# OSO-MISC-20-030_PyRadio.net
KiCad netlist of a schematic drawn in EAGLE
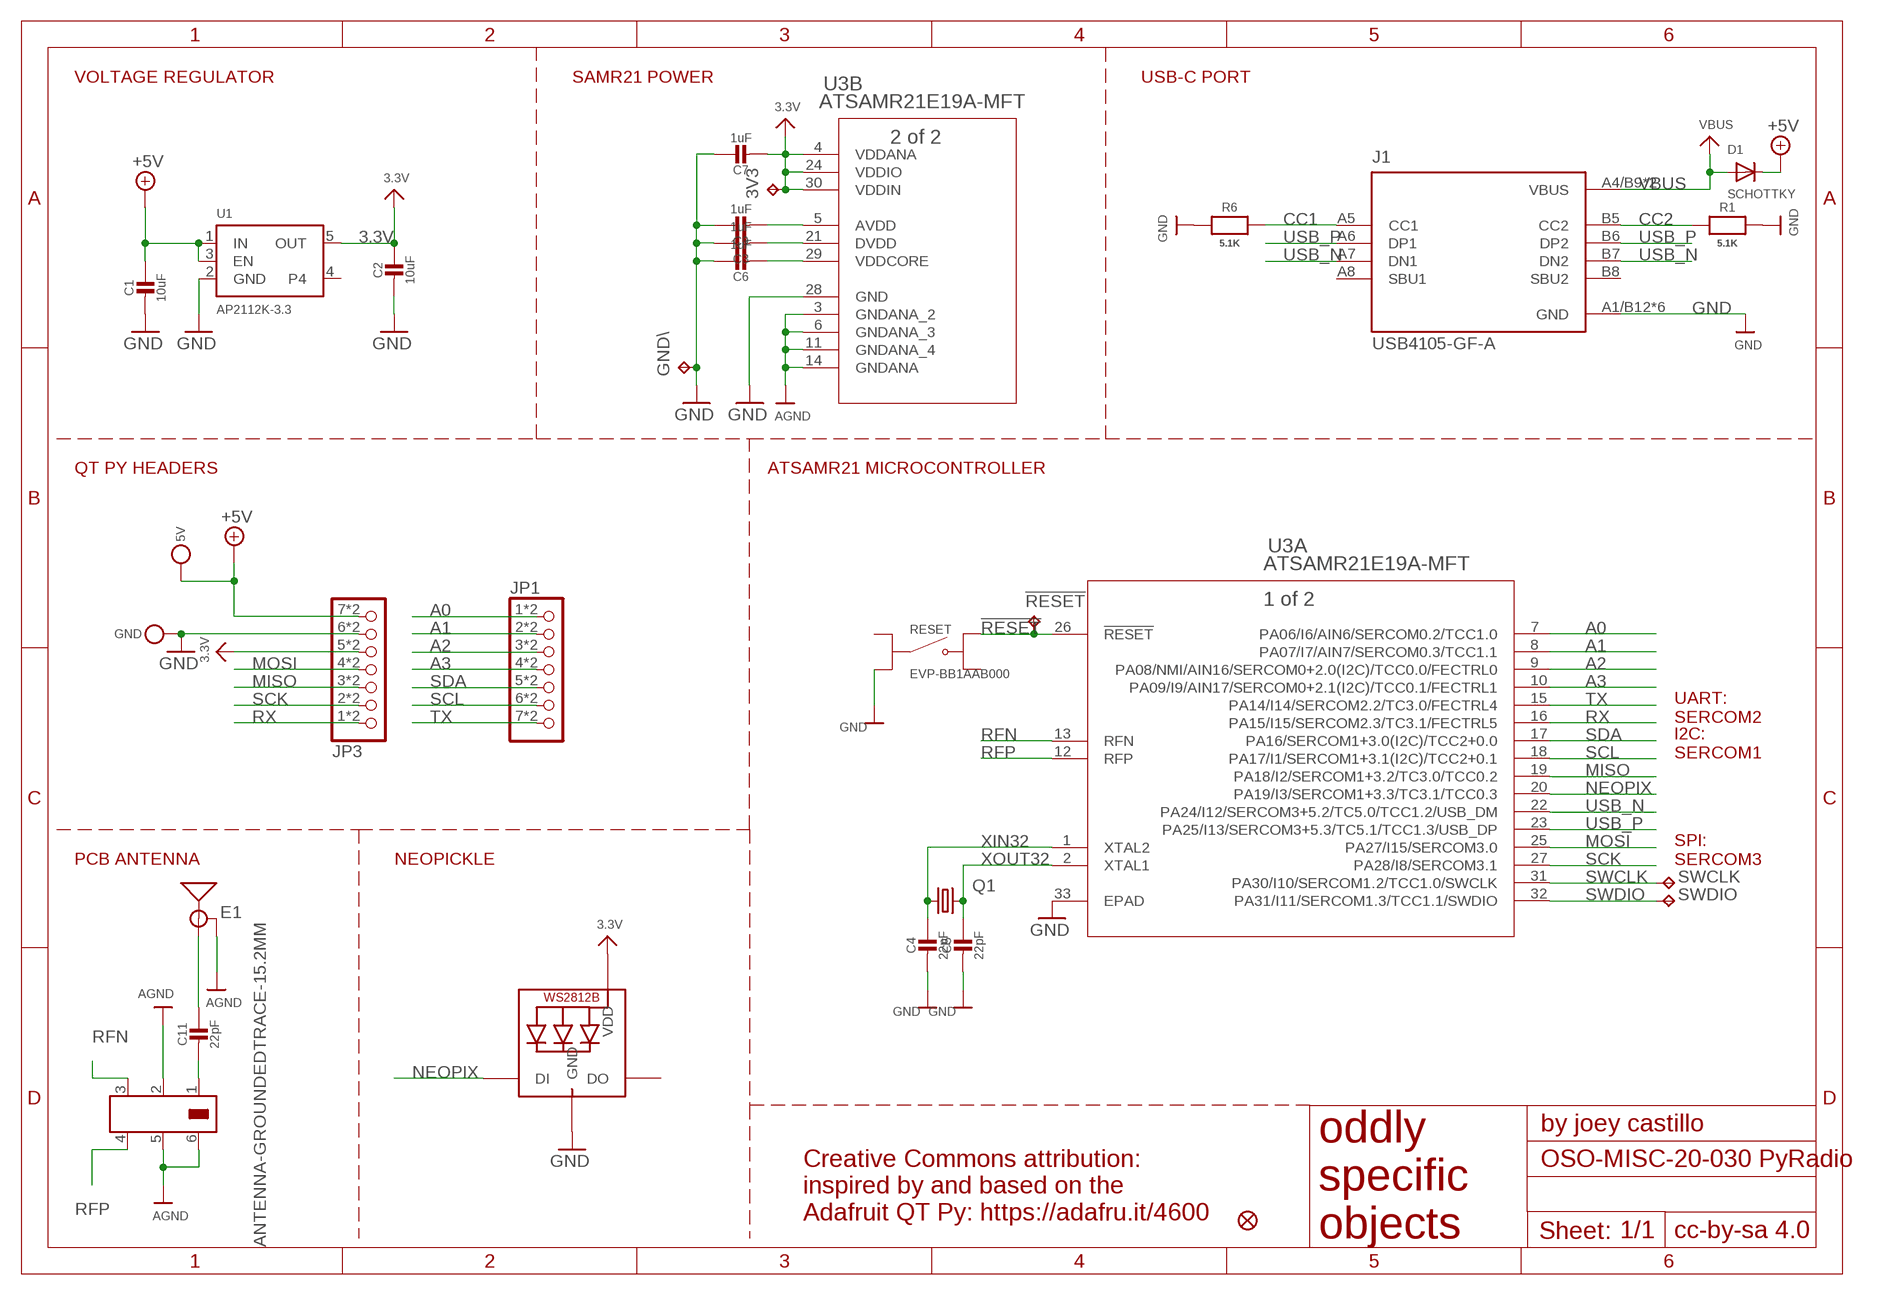
[diagram p0: schematic, sheet 1]

(export (version "E")
  (design (tool "Eeschema 10.0.6"))
  (components
    (comp (ref "!RESET")
      (value "TPTP20R")
      (footprint "eagle-import:TP20R")
      (libsource (lib "eagle-import") (part "TPTP20R"))
    )
    (comp (ref "3V3")
      (value "TPTP20R")
      (footprint "eagle-import:TP20R")
      (libsource (lib "eagle-import") (part "TPTP20R"))
    )
    (comp (ref "5V")
      (value "TESTPOINT_1X3")
      (footprint "eagle-import:TESTPOINT_RECT_1X3MM")
      (libsource (lib "eagle-import") (part "TESTPOINT_1X3"))
    )
    (comp (ref "BALUN")
      (value "JOHANSON_2450BM15A0015E")
      (footprint "eagle-import:0805_BALUN")
      (libsource (lib "eagle-import") (part "JOHANSON_2450BM15A0015E"))
    )
    (comp (ref "C1")
      (value "10uF")
      (footprint "eagle-import:_0603MP")
      (libsource (lib "eagle-import") (part "CAP_CERAMIC_0603MP"))
    )
    (comp (ref "C2")
      (value "10uF")
      (footprint "eagle-import:_0603MP")
      (libsource (lib "eagle-import") (part "CAP_CERAMIC_0603MP"))
    )
    (comp (ref "C3")
      (value "1uF")
      (footprint "eagle-import:_0603MP")
      (libsource (lib "eagle-import") (part "CAP_CERAMIC_0603MP"))
    )
    (comp (ref "C4")
      (value "22pF")
      (footprint "eagle-import:_0603MP")
      (libsource (lib "eagle-import") (part "CAP_CERAMIC_0603MP"))
    )
    (comp (ref "C5")
      (value "22pF")
      (footprint "eagle-import:_0603MP")
      (libsource (lib "eagle-import") (part "CAP_CERAMIC_0603MP"))
    )
    (comp (ref "C6")
      (value "1uF")
      (footprint "eagle-import:_0603MP")
      (libsource (lib "eagle-import") (part "CAP_CERAMIC_0603MP"))
    )
    (comp (ref "C7")
      (value "1uF")
      (footprint "eagle-import:_0603MP")
      (libsource (lib "eagle-import") (part "CAP_CERAMIC_0603MP"))
    )
    (comp (ref "C9")
      (value "1uF")
      (footprint "eagle-import:_0603MP")
      (libsource (lib "eagle-import") (part "CAP_CERAMIC_0603MP"))
    )
    (comp (ref "C11")
      (value "22pF")
      (footprint "eagle-import:_0603MP")
      (libsource (lib "eagle-import") (part "CAP_CERAMIC_0603MP"))
    )
    (comp (ref "D1")
      (value "SCHOTTKY")
      (footprint "eagle-import:SOD-323F")
      (libsource (lib "eagle-import") (part "DIODESOD-323F"))
    )
    (comp (ref "E1")
      (value "ANTENNA-GROUNDEDTRACE-15.2MM")
      (footprint "eagle-import:TRACE_ANTENNA_2.4GHZ_15.2MM")
      (libsource (lib "eagle-import") (part "ANTENNA-GROUNDEDTRACE-15.2MM"))
    )
    (comp (ref "GND")
      (value "TESTPOINT_1X3")
      (footprint "eagle-import:TESTPOINT_RECT_1X3MM")
      (libsource (lib "eagle-import") (part "TESTPOINT_1X3"))
    )
    (comp (ref "GND\\")
      (value "TPTP20R")
      (footprint "eagle-import:TP20R")
      (libsource (lib "eagle-import") (part "TPTP20R"))
    )
    (comp (ref "J1")
      (value "USB4105-GF-A")
      (footprint "eagle-import:GCT_USB4105-GF-A")
      (fields (field (name "MF") "GCT"))
      (libsource (lib "eagle-import") (part "USB4105-GF-A"))
    )
    (comp (ref "JP1")
      (value "HEADER-1X7_CASTEL")
      (footprint "eagle-import:1X07_CASTEL")
      (libsource (lib "eagle-import") (part "HEADER-1X7_CASTEL"))
    )
    (comp (ref "JP3")
      (value "HEADER-1X7_CASTEL")
      (footprint "eagle-import:1X07_CASTEL")
      (libsource (lib "eagle-import") (part "HEADER-1X7_CASTEL"))
    )
    (comp (ref "LED")
      (value "WS2812B_SK6805_1515")
      (footprint "eagle-import:SK6805_1515")
      (libsource (lib "eagle-import") (part "WS2812B_SK6805_1515"))
    )
    (comp (ref "Q1")
      (value "KX-7")
      (footprint "eagle-import:3.2X2.5_KX-7")
      (libsource (lib "eagle-import") (part "KX-7"))
    )
    (comp (ref "R1")
      (value "5.1K")
      (footprint "eagle-import:_0603MP")
      (libsource (lib "eagle-import") (part "RESISTOR_0603MP"))
    )
    (comp (ref "R6")
      (value "5.1K")
      (footprint "eagle-import:_0603MP")
      (libsource (lib "eagle-import") (part "RESISTOR_0603MP"))
    )
    (comp (ref "RESET")
      (value "EVP-BB1AAB000")
      (footprint "eagle-import:SW_EVP-BB1AAB000")
      (fields
        (field (name "DIGI-KEY_PART_NUMBER") "P124390CT-ND")
        (field (name "MF") "Panasonic Electronic Components")
      )
      (libsource (lib "eagle-import") (part "EVP-BB1AAB000"))
    )
    (comp (ref "SWCLK")
      (value "TPTP20R")
      (footprint "eagle-import:TP20R")
      (libsource (lib "eagle-import") (part "TPTP20R"))
    )
    (comp (ref "SWDIO")
      (value "TPTP20R")
      (footprint "eagle-import:TP20R")
      (libsource (lib "eagle-import") (part "TPTP20R"))
    )
    (comp (ref "U$8")
      (value "FIDUCIAL_1MM")
      (footprint "eagle-import:FIDUCIAL_1MM")
      (libsource (lib "eagle-import") (part "FIDUCIAL_1MM"))
    )
    (comp (ref "U1")
      (value "AP2112K-3.3")
      (footprint "eagle-import:SOT23-5")
      (libsource (lib "eagle-import") (part "VREG_SOT23-5"))
    )
    (comp (ref "U3")
      (value "ATSAMR21E19A-MFT")
      (footprint "eagle-import:QFN32_5X5MC_MCH")
      (fields (field (name "COPYRIGHT") "Copyright (C) 2018 Accelerated Designs. All rights reserved"))
      (libsource (lib "eagle-import") (part "ATSAMR21E19A-MFT"))
    )
  )
  (nets
    (net (code "1") (name "+5V") (class "Default")
      (node (ref "5V") (pin "P$1") (pinfunction "P$1_P$1") (pintype "bidirectional"))
      (node (ref "C1") (pin "1") (pinfunction "1_1") (pintype "passive"))
      (node (ref "D1") (pin "C") (pinfunction "C_C") (pintype "passive"))
      (node (ref "JP3") (pin "7") (pinfunction "7_7") (pintype "passive"))
      (node (ref "JP3") (pin "7C") (pinfunction "7_7C") (pintype "passive"))
      (node (ref "U1") (pin "1") (pinfunction "IN_1") (pintype "power_in"))
      (node (ref "U1") (pin "3") (pinfunction "EN_3") (pintype "input"))
    )
    (net (code "2") (name "/A0") (class "Default")
      (node (ref "JP1") (pin "1") (pinfunction "1_1") (pintype "passive"))
      (node (ref "JP1") (pin "1C") (pinfunction "1_1C") (pintype "passive"))
      (node (ref "U3") (pin "7") (pinfunction "PA06/I6/AIN6/SERCOM0.2/TCC1.0_7") (pintype "bidirectional"))
    )
    (net (code "3") (name "/A1") (class "Default")
      (node (ref "JP1") (pin "2") (pinfunction "2_2") (pintype "passive"))
      (node (ref "JP1") (pin "2C") (pinfunction "2_2C") (pintype "passive"))
      (node (ref "U3") (pin "8") (pinfunction "PA07/I7/AIN7/SERCOM0.3/TCC1.1_8") (pintype "bidirectional"))
    )
    (net (code "4") (name "/A2") (class "Default")
      (node (ref "JP1") (pin "3") (pinfunction "3_3") (pintype "passive"))
      (node (ref "JP1") (pin "3C") (pinfunction "3_3C") (pintype "passive"))
      (node (ref "U3") (pin "9") (pinfunction "PA08/NMI/AIN16/SERCOM0+2.0(I2C)/TCC0.0/FECTRL0_9") (pintype "bidirectional"))
    )
    (net (code "5") (name "/A3") (class "Default")
      (node (ref "JP1") (pin "4") (pinfunction "4_4") (pintype "passive"))
      (node (ref "JP1") (pin "4C") (pinfunction "4_4C") (pintype "passive"))
      (node (ref "U3") (pin "10") (pinfunction "PA09/I9/AIN17/SERCOM0+2.1(I2C)/TCC0.1/FECTRL1_10") (pintype "bidirectional"))
    )
    (net (code "6") (name "/CC1") (class "Default")
      (node (ref "J1") (pin "A5") (pinfunction "CC1_A5") (pintype "bidirectional"))
      (node (ref "R6") (pin "2") (pinfunction "2_2") (pintype "passive"))
    )
    (net (code "7") (name "/CC2") (class "Default")
      (node (ref "J1") (pin "B5") (pinfunction "CC2_B5") (pintype "bidirectional"))
      (node (ref "R1") (pin "1") (pinfunction "1_1") (pintype "passive"))
    )
    (net (code "8") (name "/MISO") (class "Default")
      (node (ref "JP3") (pin "3") (pinfunction "3_3") (pintype "passive"))
      (node (ref "JP3") (pin "3C") (pinfunction "3_3C") (pintype "passive"))
      (node (ref "U3") (pin "19") (pinfunction "PA18/I2/SERCOM1+3.2/TC3.0/TCC0.2_19") (pintype "bidirectional"))
    )
    (net (code "9") (name "/MOSI") (class "Default")
      (node (ref "JP3") (pin "4") (pinfunction "4_4") (pintype "passive"))
      (node (ref "JP3") (pin "4C") (pinfunction "4_4C") (pintype "passive"))
      (node (ref "U3") (pin "25") (pinfunction "PA27/I15/SERCOM3.0_25") (pintype "bidirectional"))
    )
    (net (code "10") (name "/NEOPIX") (class "Default")
      (node (ref "LED") (pin "1") (pinfunction "DI_1") (pintype "input"))
      (node (ref "U3") (pin "20") (pinfunction "PA19/I3/SERCOM1+3.3/TC3.1/TCC0.3_20") (pintype "bidirectional"))
    )
    (net (code "11") (name "/RFN") (class "Default")
      (node (ref "BALUN") (pin "3") (pinfunction "3_3") (pintype "bidirectional"))
      (node (ref "U3") (pin "13") (pinfunction "RFN_13") (pintype "passive"))
    )
    (net (code "12") (name "/RFP") (class "Default")
      (node (ref "BALUN") (pin "4") (pinfunction "4_4") (pintype "bidirectional"))
      (node (ref "U3") (pin "12") (pinfunction "RFP_12") (pintype "passive"))
    )
    (net (code "13") (name "/RX") (class "Default")
      (node (ref "JP3") (pin "1") (pinfunction "1_1") (pintype "passive"))
      (node (ref "JP3") (pin "1C") (pinfunction "1_1C") (pintype "passive"))
      (node (ref "U3") (pin "16") (pinfunction "PA15/I15/SERCOM2.3/TC3.1/FECTRL5_16") (pintype "bidirectional"))
    )
    (net (code "14") (name "/SCK") (class "Default")
      (node (ref "JP3") (pin "2") (pinfunction "2_2") (pintype "passive"))
      (node (ref "JP3") (pin "2C") (pinfunction "2_2C") (pintype "passive"))
      (node (ref "U3") (pin "27") (pinfunction "PA28/I8/SERCOM3.1_27") (pintype "bidirectional"))
    )
    (net (code "15") (name "/SCL") (class "Default")
      (node (ref "JP1") (pin "6") (pinfunction "6_6") (pintype "passive"))
      (node (ref "JP1") (pin "6C") (pinfunction "6_6C") (pintype "passive"))
      (node (ref "U3") (pin "18") (pinfunction "PA17/I1/SERCOM1+3.1(I2C)/TCC2+0.1_18") (pintype "bidirectional"))
    )
    (net (code "16") (name "/SDA") (class "Default")
      (node (ref "JP1") (pin "5") (pinfunction "5_5") (pintype "passive"))
      (node (ref "JP1") (pin "5C") (pinfunction "5_5C") (pintype "passive"))
      (node (ref "U3") (pin "17") (pinfunction "PA16/SERCOM1+3.0(I2C)/TCC2+0.0_17") (pintype "bidirectional"))
    )
    (net (code "17") (name "/SWCLK") (class "Default")
      (node (ref "SWCLK") (pin "TP") (pinfunction "TP_TP") (pintype "input"))
      (node (ref "U3") (pin "31") (pinfunction "PA30/I10/SERCOM1.2/TCC1.0/SWCLK_31") (pintype "bidirectional"))
    )
    (net (code "18") (name "/SWDIO") (class "Default")
      (node (ref "SWDIO") (pin "TP") (pinfunction "TP_TP") (pintype "input"))
      (node (ref "U3") (pin "32") (pinfunction "PA31/I11/SERCOM1.3/TCC1.1/SWDIO_32") (pintype "bidirectional"))
    )
    (net (code "19") (name "/TX") (class "Default")
      (node (ref "JP1") (pin "7") (pinfunction "7_7") (pintype "passive"))
      (node (ref "JP1") (pin "7C") (pinfunction "7_7C") (pintype "passive"))
      (node (ref "U3") (pin "15") (pinfunction "PA14/I14/SERCOM2.2/TC3.0/FECTRL4_15") (pintype "bidirectional"))
    )
    (net (code "20") (name "/USB_N") (class "Default")
      (node (ref "J1") (pin "A7") (pinfunction "DN1_A7") (pintype "bidirectional"))
      (node (ref "J1") (pin "B7") (pinfunction "DN2_B7") (pintype "bidirectional"))
      (node (ref "U3") (pin "22") (pinfunction "PA24/I12/SERCOM3+5.2/TC5.0/TCC1.2/USB_DM_22") (pintype "bidirectional"))
    )
    (net (code "21") (name "/USB_P") (class "Default")
      (node (ref "J1") (pin "A6") (pinfunction "DP1_A6") (pintype "bidirectional"))
      (node (ref "J1") (pin "B6") (pinfunction "DP2_B6") (pintype "bidirectional"))
      (node (ref "U3") (pin "23") (pinfunction "PA25/I13/SERCOM3+5.3/TC5.1/TCC1.3/USB_DP_23") (pintype "bidirectional"))
    )
    (net (code "22") (name "/XIN32") (class "Default")
      (node (ref "C4") (pin "1") (pinfunction "1_1") (pintype "passive"))
      (node (ref "Q1") (pin "1") (pinfunction "1_1") (pintype "passive"))
      (node (ref "U3") (pin "1") (pinfunction "XTAL2_1") (pintype "passive"))
    )
    (net (code "23") (name "/XOUT32") (class "Default")
      (node (ref "C5") (pin "1") (pinfunction "1_1") (pintype "passive"))
      (node (ref "Q1") (pin "3") (pinfunction "2_3") (pintype "passive"))
      (node (ref "U3") (pin "2") (pinfunction "XTAL1_2") (pintype "bidirectional"))
    )
    (net (code "24") (name "/~{RESET}") (class "Default")
      (node (ref "!RESET") (pin "TP") (pinfunction "TP_TP") (pintype "input"))
      (node (ref "RESET") (pin "B1") (pinfunction "B1_B1") (pintype "passive"))
      (node (ref "U3") (pin "26") (pinfunction "~{RESET}_26") (pintype "passive"))
    )
    (net (code "25") (name "3.3V") (class "Default")
      (node (ref "3V3") (pin "TP") (pinfunction "TP_TP") (pintype "input"))
      (node (ref "C2") (pin "1") (pinfunction "1_1") (pintype "passive"))
      (node (ref "C7") (pin "2") (pinfunction "2_2") (pintype "passive"))
      (node (ref "JP3") (pin "5") (pinfunction "5_5") (pintype "passive"))
      (node (ref "JP3") (pin "5C") (pinfunction "5_5C") (pintype "passive"))
      (node (ref "LED") (pin "2") (pinfunction "VDD_2") (pintype "power_in"))
      (node (ref "U1") (pin "5") (pinfunction "OUT_5") (pintype "power_in"))
      (node (ref "U3") (pin "24") (pinfunction "VDDIO_24") (pintype "power_in"))
      (node (ref "U3") (pin "30") (pinfunction "VDDIN_30") (pintype "power_in"))
      (node (ref "U3") (pin "4") (pinfunction "VDDANA_4") (pintype "power_in"))
    )
    (net (code "26") (name "AGND") (class "Default")
      (node (ref "BALUN") (pin "2") (pinfunction "2_2") (pintype "bidirectional"))
      (node (ref "BALUN") (pin "5") (pinfunction "5_5") (pintype "bidirectional"))
      (node (ref "BALUN") (pin "6") (pinfunction "6_6") (pintype "bidirectional"))
      (node (ref "E1") (pin "GND") (pinfunction "GND_GND") (pintype "bidirectional"))
      (node (ref "U3") (pin "11") (pinfunction "GNDANA_4_11") (pintype "passive"))
      (node (ref "U3") (pin "14") (pinfunction "GNDANA_14") (pintype "passive"))
      (node (ref "U3") (pin "3") (pinfunction "GNDANA_2_3") (pintype "passive"))
      (node (ref "U3") (pin "6") (pinfunction "GNDANA_3_6") (pintype "passive"))
    )
    (net (code "27") (name "GND") (class "Default")
      (node (ref "C1") (pin "2") (pinfunction "2_2") (pintype "passive"))
      (node (ref "C2") (pin "2") (pinfunction "2_2") (pintype "passive"))
      (node (ref "C3") (pin "1") (pinfunction "1_1") (pintype "passive"))
      (node (ref "C4") (pin "2") (pinfunction "2_2") (pintype "passive"))
      (node (ref "C5") (pin "2") (pinfunction "2_2") (pintype "passive"))
      (node (ref "C6") (pin "1") (pinfunction "1_1") (pintype "passive"))
      (node (ref "C7") (pin "1") (pinfunction "1_1") (pintype "passive"))
      (node (ref "C9") (pin "1") (pinfunction "1_1") (pintype "passive"))
      (node (ref "GND") (pin "P$1") (pinfunction "P$1_P$1") (pintype "bidirectional"))
      (node (ref "GND\\") (pin "TP") (pinfunction "TP_TP") (pintype "input"))
      (node (ref "J1") (pin "A1/B12") (pinfunction "GND_A1/B12") (pintype "power_in"))
      (node (ref "J1") (pin "B1/A12") (pinfunction "GND_B1/A12") (pintype "power_in"))
      (node (ref "J1") (pin "G1") (pinfunction "GND_G1") (pintype "power_in"))
      (node (ref "J1") (pin "G2") (pinfunction "GND_G2") (pintype "power_in"))
      (node (ref "J1") (pin "G3") (pinfunction "GND_G3") (pintype "power_in"))
      (node (ref "J1") (pin "G4") (pinfunction "GND_G4") (pintype "power_in"))
      (node (ref "JP3") (pin "6") (pinfunction "6_6") (pintype "passive"))
      (node (ref "JP3") (pin "6C") (pinfunction "6_6C") (pintype "passive"))
      (node (ref "LED") (pin "4") (pinfunction "GND_4") (pintype "power_in"))
      (node (ref "R1") (pin "2") (pinfunction "2_2") (pintype "passive"))
      (node (ref "R6") (pin "1") (pinfunction "1_1") (pintype "passive"))
      (node (ref "RESET") (pin "A2") (pinfunction "A2_A2") (pintype "passive"))
      (node (ref "U1") (pin "2") (pinfunction "GND_2") (pintype "power_in"))
      (node (ref "U3") (pin "28") (pinfunction "GND_28") (pintype "passive"))
      (node (ref "U3") (pin "33") (pinfunction "EPAD_33") (pintype "passive"))
    )
    (net (code "28") (name "Net-(BALUN-Pad1)") (class "Default")
      (node (ref "BALUN") (pin "1") (pinfunction "1_1") (pintype "bidirectional"))
      (node (ref "C11") (pin "2") (pinfunction "2_2") (pintype "passive"))
    )
    (net (code "29") (name "Net-(E1-SIGNAL)") (class "Default")
      (node (ref "C11") (pin "1") (pinfunction "1_1") (pintype "passive"))
      (node (ref "E1") (pin "ANT") (pinfunction "SIGNAL_ANT") (pintype "bidirectional"))
    )
    (net (code "30") (name "Net-(U3B-AVDD)") (class "Default")
      (node (ref "C9") (pin "2") (pinfunction "2_2") (pintype "passive"))
      (node (ref "U3") (pin "5") (pinfunction "AVDD_5") (pintype "power_in"))
    )
    (net (code "31") (name "Net-(U3B-DVDD)") (class "Default")
      (node (ref "C3") (pin "2") (pinfunction "2_2") (pintype "passive"))
      (node (ref "U3") (pin "21") (pinfunction "DVDD_21") (pintype "power_in"))
    )
    (net (code "32") (name "Net-(U3B-VDDCORE)") (class "Default")
      (node (ref "C6") (pin "2") (pinfunction "2_2") (pintype "passive"))
      (node (ref "U3") (pin "29") (pinfunction "VDDCORE_29") (pintype "power_in"))
    )
    (net (code "33") (name "VBUS") (class "Default")
      (node (ref "D1") (pin "A") (pinfunction "A_A") (pintype "passive"))
      (node (ref "J1") (pin "A4/B9") (pinfunction "VBUS_A4/B9") (pintype "power_in"))
      (node (ref "J1") (pin "B4/A9") (pinfunction "VBUS_B4/A9") (pintype "power_in"))
    )
    (net (code "34") (name "unconnected-(J1-SBU1-PadA8)") (class "Default")
      (node (ref "J1") (pin "A8") (pinfunction "SBU1_A8") (pintype "bidirectional"))
    )
    (net (code "35") (name "unconnected-(J1-SBU2-PadB8)") (class "Default")
      (node (ref "J1") (pin "B8") (pinfunction "SBU2_B8") (pintype "bidirectional"))
    )
    (net (code "36") (name "unconnected-(LED-DO-Pad3)") (class "Default")
      (node (ref "LED") (pin "3") (pinfunction "DO_3") (pintype "output"))
    )
    (net (code "37") (name "unconnected-(RESET-PadA1)") (class "Default")
      (node (ref "RESET") (pin "A1") (pinfunction "A1_A1") (pintype "passive"))
    )
    (net (code "38") (name "unconnected-(RESET-PadB2)") (class "Default")
      (node (ref "RESET") (pin "B2") (pinfunction "B2_B2") (pintype "passive"))
    )
    (net (code "39") (name "unconnected-(U1-P4-Pad4)") (class "Default")
      (node (ref "U1") (pin "4") (pinfunction "P4_4") (pintype "bidirectional"))
    )
  )
)
